# Schematic.net
KiCad netlist of a schematic drawn in EAGLE
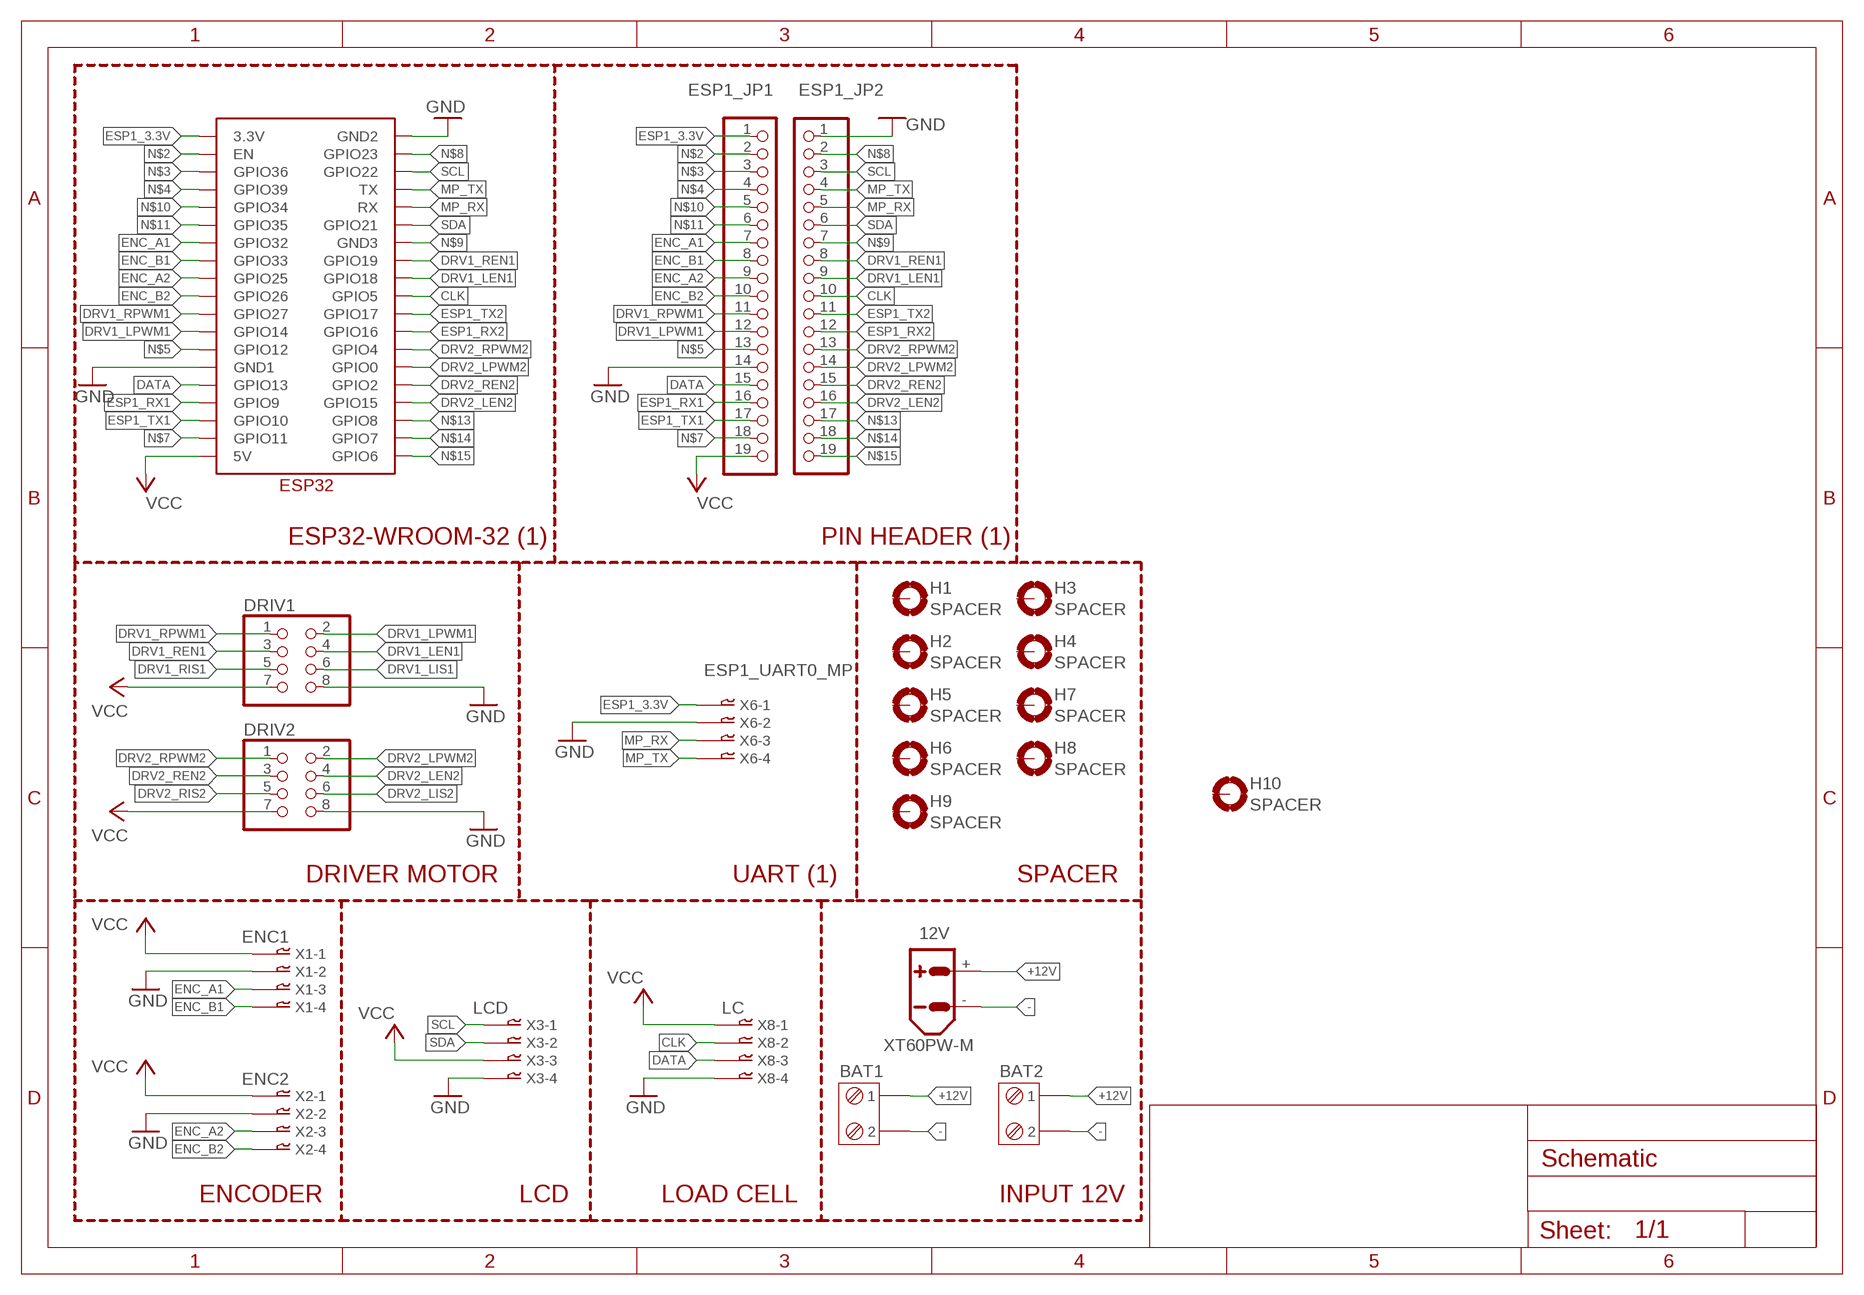
[diagram p0: schematic, sheet 1]

(export (version "E")
  (design (tool "Eeschema 10.0.6"))
  (components
    (comp (ref "12V")
      (value "XT60PW-M")
      (footprint "eagle-import:XT60PW-M")
      (libsource (lib "eagle-import") (part "XT60PW-M"))
    )
    (comp (ref "BAT1")
      (value "TERMINAL-BLOK-2P")
      (footprint "eagle-import:TERMINAL_BLOK_2P")
      (libsource (lib "eagle-import") (part "TERMINAL-BLOK-2P"))
    )
    (comp (ref "BAT2")
      (value "TERMINAL-BLOK-2P")
      (footprint "eagle-import:TERMINAL_BLOK_2P")
      (libsource (lib "eagle-import") (part "TERMINAL-BLOK-2P"))
    )
    (comp (ref "DRIV1")
      (value "PINHD-2X4")
      (footprint "eagle-import:2X04")
      (libsource (lib "eagle-import") (part "PINHD-2X4"))
    )
    (comp (ref "DRIV2")
      (value "PINHD-2X4")
      (footprint "eagle-import:2X04")
      (libsource (lib "eagle-import") (part "PINHD-2X4"))
    )
    (comp (ref "ESP1_JP1")
      (value "PINHD-1X19")
      (footprint "eagle-import:1X19")
      (libsource (lib "eagle-import") (part "PINHD-1X19"))
    )
    (comp (ref "ESP1_JP2")
      (value "PINHD-1X19")
      (footprint "eagle-import:1X19")
      (libsource (lib "eagle-import") (part "PINHD-1X19"))
    )
    (comp (ref "H1")
      (value "SPACER")
      (footprint "eagle-import:3,0-PAD")
      (libsource (lib "eagle-import") (part "SPACER"))
    )
    (comp (ref "H2")
      (value "SPACER")
      (footprint "eagle-import:3,0-PAD")
      (libsource (lib "eagle-import") (part "SPACER"))
    )
    (comp (ref "H3")
      (value "SPACER")
      (footprint "eagle-import:3,0-PAD")
      (libsource (lib "eagle-import") (part "SPACER"))
    )
    (comp (ref "H4")
      (value "SPACER")
      (footprint "eagle-import:3,0-PAD")
      (libsource (lib "eagle-import") (part "SPACER"))
    )
    (comp (ref "H5")
      (value "SPACER")
      (footprint "eagle-import:3,0-PAD")
      (libsource (lib "eagle-import") (part "SPACER"))
    )
    (comp (ref "H6")
      (value "SPACER")
      (footprint "eagle-import:3,0-PAD")
      (libsource (lib "eagle-import") (part "SPACER"))
    )
    (comp (ref "H7")
      (value "SPACER")
      (footprint "eagle-import:3,0-PAD")
      (libsource (lib "eagle-import") (part "SPACER"))
    )
    (comp (ref "H8")
      (value "SPACER")
      (footprint "eagle-import:3,0-PAD")
      (libsource (lib "eagle-import") (part "SPACER"))
    )
    (comp (ref "H9")
      (value "SPACER")
      (footprint "eagle-import:3,0-PAD")
      (libsource (lib "eagle-import") (part "SPACER"))
    )
    (comp (ref "H10")
      (value "SPACER")
      (footprint "eagle-import:3,0-PAD")
      (libsource (lib "eagle-import") (part "SPACER"))
    )
    (comp (ref "U$1")
      (value "ESP32_GRBL")
      (footprint "eagle-import:ESP32_GRBL")
      (libsource (lib "eagle-import") (part "ESP32_GRBL"))
    )
    (comp (ref "X1")
      (value "ENC1")
      (footprint "eagle-import:B4B-XH")
      (libsource (lib "eagle-import") (part "04-JST-B4B-XH-A"))
    )
    (comp (ref "X2")
      (value "ENC2")
      (footprint "eagle-import:B4B-XH")
      (libsource (lib "eagle-import") (part "04-JST-B4B-XH-A"))
    )
    (comp (ref "X3")
      (value "LCD")
      (footprint "eagle-import:B4B-XH")
      (libsource (lib "eagle-import") (part "04-JST-B4B-XH-A"))
    )
    (comp (ref "X6")
      (value "ESP1_UART0_MP")
      (footprint "eagle-import:B4B-XH")
      (libsource (lib "eagle-import") (part "04-JST-B4B-XH-A"))
    )
    (comp (ref "X8")
      (value "LC")
      (footprint "eagle-import:B4B-XH")
      (libsource (lib "eagle-import") (part "04-JST-B4B-XH-A"))
    )
  )
  (nets
    (net (code "1") (name "+12V") (class "Default")
      (node (ref "12V") (pin "+") (pinfunction "+_+") (pintype "power_in"))
      (node (ref "BAT1") (pin "1") (pinfunction "1_1") (pintype "passive"))
      (node (ref "BAT2") (pin "1") (pinfunction "1_1") (pintype "passive"))
    )
    (net (code "2") (name "-") (class "Default")
      (node (ref "12V") (pin "-") (pinfunction "-_-") (pintype "power_in"))
      (node (ref "BAT1") (pin "2") (pinfunction "2_2") (pintype "passive"))
      (node (ref "BAT2") (pin "2") (pinfunction "2_2") (pintype "passive"))
    )
    (net (code "3") (name "CLK") (class "Default")
      (node (ref "ESP1_JP2") (pin "10") (pinfunction "10_10") (pintype "passive"))
      (node (ref "U$1") (pin "GPIO5") (pinfunction "GPIO5_GPIO5") (pintype "bidirectional"))
      (node (ref "X8") (pin "P$2") (pinfunction "1_P$2") (pintype "passive"))
    )
    (net (code "4") (name "DATA") (class "Default")
      (node (ref "ESP1_JP1") (pin "15") (pinfunction "15_15") (pintype "passive"))
      (node (ref "U$1") (pin "GPIO13") (pinfunction "GPIO13_GPIO13") (pintype "bidirectional"))
      (node (ref "X8") (pin "P$3") (pinfunction "1_P$3") (pintype "passive"))
    )
    (net (code "5") (name "DRV1_LEN1") (class "Default")
      (node (ref "DRIV1") (pin "4") (pinfunction "4_4") (pintype "passive"))
      (node (ref "ESP1_JP2") (pin "9") (pinfunction "9_9") (pintype "passive"))
      (node (ref "U$1") (pin "GPIO18") (pinfunction "GPIO18_GPIO18") (pintype "bidirectional"))
    )
    (net (code "6") (name "DRV1_LIS1") (class "Default")
      (node (ref "DRIV1") (pin "6") (pinfunction "6_6") (pintype "passive"))
    )
    (net (code "7") (name "DRV1_LPWM1") (class "Default")
      (node (ref "DRIV1") (pin "2") (pinfunction "2_2") (pintype "passive"))
      (node (ref "ESP1_JP1") (pin "12") (pinfunction "12_12") (pintype "passive"))
      (node (ref "U$1") (pin "GPIO14") (pinfunction "GPIO14_GPIO14") (pintype "bidirectional"))
    )
    (net (code "8") (name "DRV1_REN1") (class "Default")
      (node (ref "DRIV1") (pin "3") (pinfunction "3_3") (pintype "passive"))
      (node (ref "ESP1_JP2") (pin "8") (pinfunction "8_8") (pintype "passive"))
      (node (ref "U$1") (pin "GPIO19") (pinfunction "GPIO19_GPIO19") (pintype "bidirectional"))
    )
    (net (code "9") (name "DRV1_RIS1") (class "Default")
      (node (ref "DRIV1") (pin "5") (pinfunction "5_5") (pintype "passive"))
    )
    (net (code "10") (name "DRV1_RPWM1") (class "Default")
      (node (ref "DRIV1") (pin "1") (pinfunction "1_1") (pintype "passive"))
      (node (ref "ESP1_JP1") (pin "11") (pinfunction "11_11") (pintype "passive"))
      (node (ref "U$1") (pin "GPIO27") (pinfunction "GPIO27_GPIO27") (pintype "bidirectional"))
    )
    (net (code "11") (name "DRV2_LEN2") (class "Default")
      (node (ref "DRIV2") (pin "4") (pinfunction "4_4") (pintype "passive"))
      (node (ref "ESP1_JP2") (pin "16") (pinfunction "16_16") (pintype "passive"))
      (node (ref "U$1") (pin "GPIO15") (pinfunction "GPIO15_GPIO15") (pintype "bidirectional"))
    )
    (net (code "12") (name "DRV2_LIS2") (class "Default")
      (node (ref "DRIV2") (pin "6") (pinfunction "6_6") (pintype "passive"))
    )
    (net (code "13") (name "DRV2_LPWM2") (class "Default")
      (node (ref "DRIV2") (pin "2") (pinfunction "2_2") (pintype "passive"))
      (node (ref "ESP1_JP2") (pin "14") (pinfunction "14_14") (pintype "passive"))
      (node (ref "U$1") (pin "GPIO0") (pinfunction "GPIO0_GPIO0") (pintype "bidirectional"))
    )
    (net (code "14") (name "DRV2_REN2") (class "Default")
      (node (ref "DRIV2") (pin "3") (pinfunction "3_3") (pintype "passive"))
      (node (ref "ESP1_JP2") (pin "15") (pinfunction "15_15") (pintype "passive"))
      (node (ref "U$1") (pin "GPIO2") (pinfunction "GPIO2_GPIO2") (pintype "bidirectional"))
    )
    (net (code "15") (name "DRV2_RIS2") (class "Default")
      (node (ref "DRIV2") (pin "5") (pinfunction "5_5") (pintype "passive"))
    )
    (net (code "16") (name "DRV2_RPWM2") (class "Default")
      (node (ref "DRIV2") (pin "1") (pinfunction "1_1") (pintype "passive"))
      (node (ref "ESP1_JP2") (pin "13") (pinfunction "13_13") (pintype "passive"))
      (node (ref "U$1") (pin "GPIO4") (pinfunction "GPIO4_GPIO4") (pintype "bidirectional"))
    )
    (net (code "17") (name "ENC_A1") (class "Default")
      (node (ref "ESP1_JP1") (pin "7") (pinfunction "7_7") (pintype "passive"))
      (node (ref "U$1") (pin "GPIO32") (pinfunction "GPIO32_GPIO32") (pintype "bidirectional"))
      (node (ref "X1") (pin "P$3") (pinfunction "1_P$3") (pintype "passive"))
    )
    (net (code "18") (name "ENC_A2") (class "Default")
      (node (ref "ESP1_JP1") (pin "9") (pinfunction "9_9") (pintype "passive"))
      (node (ref "U$1") (pin "GPIO25") (pinfunction "GPIO25_GPIO25") (pintype "bidirectional"))
      (node (ref "X2") (pin "P$3") (pinfunction "1_P$3") (pintype "passive"))
    )
    (net (code "19") (name "ENC_B1") (class "Default")
      (node (ref "ESP1_JP1") (pin "8") (pinfunction "8_8") (pintype "passive"))
      (node (ref "U$1") (pin "GPIO33") (pinfunction "GPIO33_GPIO33") (pintype "bidirectional"))
      (node (ref "X1") (pin "P$4") (pinfunction "1_P$4") (pintype "passive"))
    )
    (net (code "20") (name "ENC_B2") (class "Default")
      (node (ref "ESP1_JP1") (pin "10") (pinfunction "10_10") (pintype "passive"))
      (node (ref "U$1") (pin "GPIO26") (pinfunction "GPIO26_GPIO26") (pintype "bidirectional"))
      (node (ref "X2") (pin "P$4") (pinfunction "1_P$4") (pintype "passive"))
    )
    (net (code "21") (name "ESP1_3.3V") (class "Default")
      (node (ref "ESP1_JP1") (pin "1") (pinfunction "1_1") (pintype "passive"))
      (node (ref "U$1") (pin "3.3V") (pinfunction "3.3V_3.3V") (pintype "bidirectional"))
      (node (ref "X6") (pin "P$1") (pinfunction "1_P$1") (pintype "passive"))
    )
    (net (code "22") (name "ESP1_RX1") (class "Default")
      (node (ref "ESP1_JP1") (pin "16") (pinfunction "16_16") (pintype "passive"))
      (node (ref "U$1") (pin "GPIO9") (pinfunction "GPIO9_GPIO9") (pintype "bidirectional"))
    )
    (net (code "23") (name "ESP1_RX2") (class "Default")
      (node (ref "ESP1_JP2") (pin "12") (pinfunction "12_12") (pintype "passive"))
      (node (ref "U$1") (pin "GPIO16") (pinfunction "GPIO16_GPIO16") (pintype "bidirectional"))
    )
    (net (code "24") (name "ESP1_TX1") (class "Default")
      (node (ref "ESP1_JP1") (pin "17") (pinfunction "17_17") (pintype "passive"))
      (node (ref "U$1") (pin "GPIO10") (pinfunction "GPIO10_GPIO10") (pintype "bidirectional"))
    )
    (net (code "25") (name "ESP1_TX2") (class "Default")
      (node (ref "ESP1_JP2") (pin "11") (pinfunction "11_11") (pintype "passive"))
      (node (ref "U$1") (pin "GPIO17") (pinfunction "GPIO17_GPIO17") (pintype "bidirectional"))
    )
    (net (code "26") (name "GND") (class "Default")
      (node (ref "DRIV1") (pin "8") (pinfunction "8_8") (pintype "passive"))
      (node (ref "DRIV2") (pin "8") (pinfunction "8_8") (pintype "passive"))
      (node (ref "ESP1_JP1") (pin "14") (pinfunction "14_14") (pintype "passive"))
      (node (ref "ESP1_JP2") (pin "1") (pinfunction "1_1") (pintype "passive"))
      (node (ref "U$1") (pin "GND1") (pinfunction "GND1_GND1") (pintype "bidirectional"))
      (node (ref "U$1") (pin "GND2") (pinfunction "GND2_GND2") (pintype "bidirectional"))
      (node (ref "X1") (pin "P$2") (pinfunction "1_P$2") (pintype "passive"))
      (node (ref "X2") (pin "P$2") (pinfunction "1_P$2") (pintype "passive"))
      (node (ref "X3") (pin "P$4") (pinfunction "1_P$4") (pintype "passive"))
      (node (ref "X6") (pin "P$2") (pinfunction "1_P$2") (pintype "passive"))
      (node (ref "X8") (pin "P$4") (pinfunction "1_P$4") (pintype "passive"))
    )
    (net (code "27") (name "MP_RX") (class "Default")
      (node (ref "ESP1_JP2") (pin "5") (pinfunction "5_5") (pintype "passive"))
      (node (ref "U$1") (pin "RX") (pinfunction "RX_RX") (pintype "bidirectional"))
      (node (ref "X6") (pin "P$3") (pinfunction "1_P$3") (pintype "passive"))
    )
    (net (code "28") (name "MP_TX") (class "Default")
      (node (ref "ESP1_JP2") (pin "4") (pinfunction "4_4") (pintype "passive"))
      (node (ref "U$1") (pin "TX") (pinfunction "TX_TX") (pintype "bidirectional"))
      (node (ref "X6") (pin "P$4") (pinfunction "1_P$4") (pintype "passive"))
    )
    (net (code "29") (name "N$2") (class "Default")
      (node (ref "ESP1_JP1") (pin "2") (pinfunction "2_2") (pintype "passive"))
      (node (ref "U$1") (pin "EN") (pinfunction "EN_EN") (pintype "bidirectional"))
    )
    (net (code "30") (name "N$3") (class "Default")
      (node (ref "ESP1_JP1") (pin "3") (pinfunction "3_3") (pintype "passive"))
      (node (ref "U$1") (pin "GPIO36") (pinfunction "GPIO36_GPIO36") (pintype "bidirectional"))
    )
    (net (code "31") (name "N$4") (class "Default")
      (node (ref "ESP1_JP1") (pin "4") (pinfunction "4_4") (pintype "passive"))
      (node (ref "U$1") (pin "GPIO39") (pinfunction "GPIO39_GPIO39") (pintype "bidirectional"))
    )
    (net (code "32") (name "N$5") (class "Default")
      (node (ref "ESP1_JP1") (pin "13") (pinfunction "13_13") (pintype "passive"))
      (node (ref "U$1") (pin "GPIO12") (pinfunction "GPIO12_GPIO12") (pintype "bidirectional"))
    )
    (net (code "33") (name "N$7") (class "Default")
      (node (ref "ESP1_JP1") (pin "18") (pinfunction "18_18") (pintype "passive"))
      (node (ref "U$1") (pin "GPIO11") (pinfunction "GPIO11_GPIO11") (pintype "bidirectional"))
    )
    (net (code "34") (name "N$8") (class "Default")
      (node (ref "ESP1_JP2") (pin "2") (pinfunction "2_2") (pintype "passive"))
      (node (ref "U$1") (pin "GPIO23") (pinfunction "GPIO23_GPIO23") (pintype "bidirectional"))
    )
    (net (code "35") (name "N$9") (class "Default")
      (node (ref "ESP1_JP2") (pin "7") (pinfunction "7_7") (pintype "passive"))
      (node (ref "U$1") (pin "GND3") (pinfunction "GND3_GND3") (pintype "bidirectional"))
    )
    (net (code "36") (name "N$10") (class "Default")
      (node (ref "ESP1_JP1") (pin "5") (pinfunction "5_5") (pintype "passive"))
      (node (ref "U$1") (pin "GPIO34") (pinfunction "GPIO34_GPIO34") (pintype "bidirectional"))
    )
    (net (code "37") (name "N$11") (class "Default")
      (node (ref "ESP1_JP1") (pin "6") (pinfunction "6_6") (pintype "passive"))
      (node (ref "U$1") (pin "GPIO35") (pinfunction "GPIO35_GPIO35") (pintype "bidirectional"))
    )
    (net (code "38") (name "N$13") (class "Default")
      (node (ref "ESP1_JP2") (pin "17") (pinfunction "17_17") (pintype "passive"))
      (node (ref "U$1") (pin "GPIO8") (pinfunction "GPIO8_GPIO8") (pintype "bidirectional"))
    )
    (net (code "39") (name "N$14") (class "Default")
      (node (ref "ESP1_JP2") (pin "18") (pinfunction "18_18") (pintype "passive"))
      (node (ref "U$1") (pin "GPIO7") (pinfunction "GPIO7_GPIO7") (pintype "bidirectional"))
    )
    (net (code "40") (name "N$15") (class "Default")
      (node (ref "ESP1_JP2") (pin "19") (pinfunction "19_19") (pintype "passive"))
      (node (ref "U$1") (pin "GPIO6") (pinfunction "GPIO6_GPIO6") (pintype "bidirectional"))
    )
    (net (code "41") (name "SCL") (class "Default")
      (node (ref "ESP1_JP2") (pin "3") (pinfunction "3_3") (pintype "passive"))
      (node (ref "U$1") (pin "GPIO22") (pinfunction "GPIO22_GPIO22") (pintype "bidirectional"))
      (node (ref "X3") (pin "P$1") (pinfunction "1_P$1") (pintype "passive"))
    )
    (net (code "42") (name "SDA") (class "Default")
      (node (ref "ESP1_JP2") (pin "6") (pinfunction "6_6") (pintype "passive"))
      (node (ref "U$1") (pin "GPIO21") (pinfunction "GPIO21_GPIO21") (pintype "bidirectional"))
      (node (ref "X3") (pin "P$2") (pinfunction "1_P$2") (pintype "passive"))
    )
    (net (code "43") (name "VCC") (class "Default")
      (node (ref "DRIV1") (pin "7") (pinfunction "7_7") (pintype "passive"))
      (node (ref "DRIV2") (pin "7") (pinfunction "7_7") (pintype "passive"))
      (node (ref "ESP1_JP1") (pin "19") (pinfunction "19_19") (pintype "passive"))
      (node (ref "U$1") (pin "5V") (pinfunction "5V_5V") (pintype "bidirectional"))
      (node (ref "X1") (pin "P$1") (pinfunction "1_P$1") (pintype "passive"))
      (node (ref "X2") (pin "P$1") (pinfunction "1_P$1") (pintype "passive"))
      (node (ref "X3") (pin "P$3") (pinfunction "1_P$3") (pintype "passive"))
      (node (ref "X8") (pin "P$1") (pinfunction "1_P$1") (pintype "passive"))
    )
    (net (code "44") (name "unconnected-(H1-MOUNT-PadB3,0)") (class "Default")
      (node (ref "H1") (pin "B3,0") (pinfunction "MOUNT_B3,0") (pintype "passive"))
    )
    (net (code "45") (name "unconnected-(H2-MOUNT-PadB3,0)") (class "Default")
      (node (ref "H2") (pin "B3,0") (pinfunction "MOUNT_B3,0") (pintype "passive"))
    )
    (net (code "46") (name "unconnected-(H3-MOUNT-PadB3,0)") (class "Default")
      (node (ref "H3") (pin "B3,0") (pinfunction "MOUNT_B3,0") (pintype "passive"))
    )
    (net (code "47") (name "unconnected-(H4-MOUNT-PadB3,0)") (class "Default")
      (node (ref "H4") (pin "B3,0") (pinfunction "MOUNT_B3,0") (pintype "passive"))
    )
    (net (code "48") (name "unconnected-(H5-MOUNT-PadB3,0)") (class "Default")
      (node (ref "H5") (pin "B3,0") (pinfunction "MOUNT_B3,0") (pintype "passive"))
    )
    (net (code "49") (name "unconnected-(H6-MOUNT-PadB3,0)") (class "Default")
      (node (ref "H6") (pin "B3,0") (pinfunction "MOUNT_B3,0") (pintype "passive"))
    )
    (net (code "50") (name "unconnected-(H7-MOUNT-PadB3,0)") (class "Default")
      (node (ref "H7") (pin "B3,0") (pinfunction "MOUNT_B3,0") (pintype "passive"))
    )
    (net (code "51") (name "unconnected-(H8-MOUNT-PadB3,0)") (class "Default")
      (node (ref "H8") (pin "B3,0") (pinfunction "MOUNT_B3,0") (pintype "passive"))
    )
    (net (code "52") (name "unconnected-(H9-MOUNT-PadB3,0)") (class "Default")
      (node (ref "H9") (pin "B3,0") (pinfunction "MOUNT_B3,0") (pintype "passive"))
    )
    (net (code "53") (name "unconnected-(H10-MOUNT-PadB3,0)") (class "Default")
      (node (ref "H10") (pin "B3,0") (pinfunction "MOUNT_B3,0") (pintype "passive"))
    )
  )
)
